# SD.net
KiCad netlist of a schematic drawn in Altium Designer
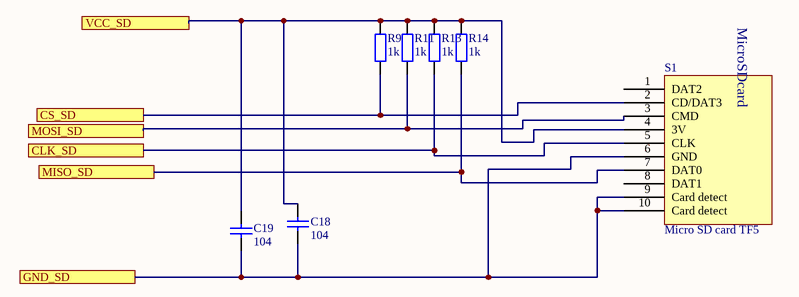
[diagram p0: SD.SchDoc]

(export (version "E")
  (design (tool "Eeschema 10.0.6"))
  (components
    (comp (ref "C18")
      (value "104")
      (footprint "tu 0805")
      (description "Dán")
      (libsource (lib "BKRES_Schlib") (part "Tu 0805 104 50V 10%"))
    )
    (comp (ref "C19")
      (value "104")
      (footprint "tu 0805")
      (description "Dán")
      (libsource (lib "BKRES_Schlib") (part "Tu 0805 104 50V 10%"))
    )
    (comp (ref "R9")
      (value "1k")
      (footprint "tro smd 0805")
      (description "Dán")
      (libsource (lib "BKRES_Schlib") (part "Tro 0805 1% 1k"))
    )
    (comp (ref "R11")
      (value "1k")
      (footprint "tro smd 0805")
      (description "Dán")
      (libsource (lib "BKRES_Schlib") (part "Tro 0805 1% 1k"))
    )
    (comp (ref "R13")
      (value "1k")
      (footprint "tro smd 0805")
      (description "Dán")
      (libsource (lib "BKRES_Schlib") (part "Tro 0805 1% 1k"))
    )
    (comp (ref "R14")
      (value "1k")
      (footprint "tro smd 0805")
      (description "Dán")
      (libsource (lib "BKRES_Schlib") (part "Tro 0805 1% 1k"))
    )
    (comp (ref "S1")
      (value "Micro SD card TF5")
      (footprint "MicroSD TF V5")
      (libsource (lib "Altium_Lib_by_KhueNguyenCreator") (part "Micro SD card TF5"))
    )
  )
  (nets
    (net (code "1") (name "/CLK_SD") (class "Default")
      (node (ref "R13") (pin "1") (pinfunction "1_1") (pintype "passive"))
      (node (ref "S1") (pin "5") (pinfunction "CLK_5") (pintype "passive"))
    )
    (net (code "2") (name "/CS_SD") (class "Default")
      (node (ref "R9") (pin "2") (pinfunction "2_2") (pintype "passive"))
      (node (ref "S1") (pin "2") (pinfunction "CD/DAT3_2") (pintype "passive"))
    )
    (net (code "3") (name "/GND_SD") (class "Default")
      (node (ref "C18") (pin "2") (pinfunction "2_2") (pintype "passive"))
      (node (ref "C19") (pin "2") (pinfunction "2_2") (pintype "passive"))
      (node (ref "S1") (pin "10") (pinfunction "Card_detect_10") (pintype "passive"))
      (node (ref "S1") (pin "6") (pinfunction "GND_6") (pintype "passive"))
      (node (ref "S1") (pin "9") (pinfunction "Card_detect_9") (pintype "passive"))
    )
    (net (code "4") (name "/MISO_SD") (class "Default")
      (node (ref "R14") (pin "1") (pinfunction "1_1") (pintype "passive"))
      (node (ref "S1") (pin "7") (pinfunction "DAT0_7") (pintype "passive"))
    )
    (net (code "5") (name "/MOSI_SD") (class "Default")
      (node (ref "R11") (pin "1") (pinfunction "1_1") (pintype "passive"))
      (node (ref "S1") (pin "3") (pinfunction "CMD_3") (pintype "passive"))
    )
    (net (code "6") (name "/VCC_SD") (class "Default")
      (node (ref "C18") (pin "1") (pinfunction "1_1") (pintype "passive"))
      (node (ref "C19") (pin "1") (pinfunction "1_1") (pintype "passive"))
      (node (ref "R11") (pin "2") (pinfunction "2_2") (pintype "passive"))
      (node (ref "R13") (pin "2") (pinfunction "2_2") (pintype "passive"))
      (node (ref "R14") (pin "2") (pinfunction "2_2") (pintype "passive"))
      (node (ref "R9") (pin "1") (pinfunction "1_1") (pintype "passive"))
      (node (ref "S1") (pin "4") (pinfunction "3V_4") (pintype "passive"))
    )
    (net (code "7") (name "unconnected-(S1-DAT1-Pad8)") (class "Default")
      (node (ref "S1") (pin "8") (pinfunction "DAT1_8") (pintype "passive"))
    )
    (net (code "8") (name "unconnected-(S1-DAT2-Pad1)") (class "Default")
      (node (ref "S1") (pin "1") (pinfunction "DAT2_1") (pintype "passive"))
    )
  )
)
